# ArduinoUnoShield.net
KiCad netlist of a schematic drawn in Altium Designer
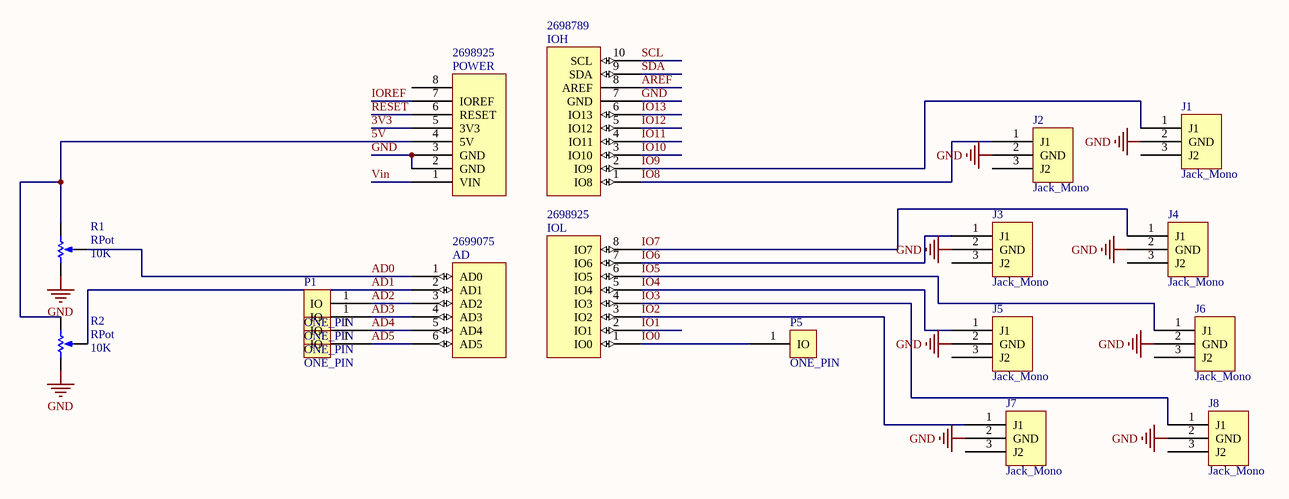
[diagram p0: ArduinoUnoShield.SchDoc]

(export (version "E")
  (design (tool "Eeschema 10.0.6"))
  (components
    (comp (ref "AD")
      (value "AD")
      (footprint "Header:Header 6x1 8.5mm")
      (fields (field (name "SUPPLIER PART NUMBER 4") "2699075"))
      (libsource (lib "Header") (part "AD"))
    )
    (comp (ref "IOH")
      (value "IOH")
      (footprint "Header:Header 10x1 8.5mm")
      (fields (field (name "SUPPLIER PART NUMBER 3") "2698789"))
      (libsource (lib "Header") (part "IOH"))
    )
    (comp (ref "IOL")
      (value "IOL")
      (footprint "Header 8x1 8.5mm")
      (fields (field (name "SUPPLIER PART NUMBER 4") "2698925"))
      (libsource (lib "Header") (part "IOL"))
    )
    (comp (ref "J1") (value "Jack_Mono") (footprint "JACK_MONO") (libsource (lib "Jack") (part "Jack_Mono")))
    (comp (ref "J2") (value "Jack_Mono") (footprint "JACK_MONO") (libsource (lib "Jack") (part "Jack_Mono")))
    (comp (ref "J3") (value "Jack_Mono") (footprint "JACK_MONO") (libsource (lib "Jack") (part "Jack_Mono")))
    (comp (ref "J4") (value "Jack_Mono") (footprint "JACK_MONO") (libsource (lib "Jack") (part "Jack_Mono")))
    (comp (ref "J5") (value "Jack_Mono") (footprint "JACK_MONO") (libsource (lib "Jack") (part "Jack_Mono")))
    (comp (ref "J6") (value "Jack_Mono") (footprint "JACK_MONO") (libsource (lib "Jack") (part "Jack_Mono")))
    (comp (ref "J7") (value "Jack_Mono") (footprint "JACK_MONO") (libsource (lib "Jack") (part "Jack_Mono")))
    (comp (ref "J8") (value "Jack_Mono") (footprint "JACK_MONO") (libsource (lib "Jack") (part "Jack_Mono")))
    (comp (ref "P1") (value "ONE_PIN") (footprint "ONE_PIN") (libsource (lib "") (part "ONE_PIN_1")))
    (comp (ref "P2") (value "ONE_PIN") (footprint "ONE_PIN") (libsource (lib "") (part "ONE_PIN_1")))
    (comp (ref "P3") (value "ONE_PIN") (footprint "ONE_PIN") (libsource (lib "") (part "ONE_PIN_1")))
    (comp (ref "P4") (value "ONE_PIN") (footprint "ONE_PIN") (libsource (lib "") (part "ONE_PIN_1")))
    (comp (ref "P5") (value "ONE_PIN") (footprint "ONE_PIN") (libsource (lib "OnePin") (part "ONE_PIN")))
    (comp (ref "POWER")
      (value "POWER_UNO")
      (footprint "Header 8x1 8.5mm")
      (fields (field (name "SUPPLIER PART NUMBER 4") "2698925"))
      (libsource (lib "Header") (part "POWER_UNO"))
    )
    (comp (ref "R1")
      (value "RPot")
      (footprint "VR5")
      (description "Potentiometer")
      (fields (field (name "ALTIUM_VALUE") "10K") (field (name "PUBLISHER") "Altium Limited"))
      (libsource (lib "Miscellaneous Devices") (part "RPot"))
    )
    (comp (ref "R2")
      (value "RPot")
      (footprint "VR5")
      (description "Potentiometer")
      (fields (field (name "ALTIUM_VALUE") "10K") (field (name "PUBLISHER") "Altium Limited"))
      (libsource (lib "Miscellaneous Devices") (part "RPot"))
    )
  )
  (nets
    (net (code "1") (name "/3V3") (class "Default")
      (node (ref "POWER") (pin "5") (pinfunction "3V3_5") (pintype "power_in"))
    )
    (net (code "2") (name "/5V") (class "Default")
      (node (ref "POWER") (pin "4") (pinfunction "5V_4") (pintype "power_in"))
      (node (ref "R1") (pin "2") (pinfunction "BOT_2") (pintype "passive"))
      (node (ref "R2") (pin "2") (pinfunction "BOT_2") (pintype "passive"))
    )
    (net (code "4") (name "/AD0") (class "Default")
      (node (ref "AD") (pin "1") (pinfunction "AD0_1") (pintype "bidirectional"))
      (node (ref "R1") (pin "3") (pinfunction "TAP_3") (pintype "passive"))
    )
    (net (code "5") (name "/AD1") (class "Default")
      (node (ref "AD") (pin "2") (pinfunction "AD1_2") (pintype "bidirectional"))
      (node (ref "R2") (pin "3") (pinfunction "TAP_3") (pintype "passive"))
    )
    (net (code "6") (name "/AD2") (class "Default")
      (node (ref "AD") (pin "3") (pinfunction "AD2_3") (pintype "bidirectional"))
      (node (ref "P1") (pin "1") (pinfunction "IO_1") (pintype "passive"))
    )
    (net (code "7") (name "/AD3") (class "Default")
      (node (ref "AD") (pin "4") (pinfunction "AD3_4") (pintype "bidirectional"))
      (node (ref "P2") (pin "1") (pinfunction "IO_1") (pintype "passive"))
    )
    (net (code "8") (name "/AD4") (class "Default")
      (node (ref "AD") (pin "5") (pinfunction "AD4_5") (pintype "bidirectional"))
      (node (ref "P3") (pin "1") (pinfunction "IO_1") (pintype "passive"))
    )
    (net (code "9") (name "/AD5") (class "Default")
      (node (ref "AD") (pin "6") (pinfunction "AD5_6") (pintype "bidirectional"))
      (node (ref "P4") (pin "1") (pinfunction "IO_1") (pintype "passive"))
    )
    (net (code "10") (name "/AREF") (class "Default")
      (node (ref "IOH") (pin "8") (pinfunction "AREF_8") (pintype "passive"))
    )
    (net (code "11") (name "/IO0") (class "Default")
      (node (ref "IOL") (pin "1") (pinfunction "IO0_1") (pintype "bidirectional"))
      (node (ref "P5") (pin "1") (pinfunction "IO_1") (pintype "passive"))
    )
    (net (code "12") (name "/IO1") (class "Default")
      (node (ref "IOL") (pin "2") (pinfunction "IO1_2") (pintype "bidirectional"))
    )
    (net (code "13") (name "/IO2") (class "Default")
      (node (ref "IOL") (pin "3") (pinfunction "IO2_3") (pintype "bidirectional"))
      (node (ref "J7") (pin "1") (pinfunction "J1_1") (pintype "passive"))
    )
    (net (code "14") (name "/IO3") (class "Default")
      (node (ref "IOL") (pin "4") (pinfunction "IO3_4") (pintype "bidirectional"))
      (node (ref "J8") (pin "1") (pinfunction "J1_1") (pintype "passive"))
    )
    (net (code "15") (name "/IO4") (class "Default")
      (node (ref "IOL") (pin "5") (pinfunction "IO4_5") (pintype "bidirectional"))
      (node (ref "J5") (pin "1") (pinfunction "J1_1") (pintype "passive"))
    )
    (net (code "16") (name "/IO5") (class "Default")
      (node (ref "IOL") (pin "6") (pinfunction "IO5_6") (pintype "bidirectional"))
      (node (ref "J6") (pin "1") (pinfunction "J1_1") (pintype "passive"))
    )
    (net (code "17") (name "/IO6") (class "Default")
      (node (ref "IOL") (pin "7") (pinfunction "IO6_7") (pintype "bidirectional"))
      (node (ref "J3") (pin "1") (pinfunction "J1_1") (pintype "passive"))
    )
    (net (code "18") (name "/IO7") (class "Default")
      (node (ref "IOL") (pin "8") (pinfunction "IO7_8") (pintype "bidirectional"))
      (node (ref "J4") (pin "1") (pinfunction "J1_1") (pintype "passive"))
    )
    (net (code "19") (name "/IO8") (class "Default")
      (node (ref "IOH") (pin "1") (pinfunction "IO8_1") (pintype "bidirectional"))
      (node (ref "J2") (pin "1") (pinfunction "J1_1") (pintype "passive"))
    )
    (net (code "20") (name "/IO9") (class "Default")
      (node (ref "IOH") (pin "2") (pinfunction "IO9_2") (pintype "bidirectional"))
      (node (ref "J1") (pin "1") (pinfunction "J1_1") (pintype "passive"))
    )
    (net (code "21") (name "/IO10") (class "Default")
      (node (ref "IOH") (pin "3") (pinfunction "IO10_3") (pintype "bidirectional"))
    )
    (net (code "22") (name "/IO11") (class "Default")
      (node (ref "IOH") (pin "4") (pinfunction "IO11_4") (pintype "bidirectional"))
    )
    (net (code "23") (name "/IO12") (class "Default")
      (node (ref "IOH") (pin "5") (pinfunction "IO12_5") (pintype "bidirectional"))
    )
    (net (code "24") (name "/IO13") (class "Default")
      (node (ref "IOH") (pin "6") (pinfunction "IO13_6") (pintype "bidirectional"))
    )
    (net (code "25") (name "/IOREF") (class "Default")
      (node (ref "POWER") (pin "7") (pinfunction "IOREF_7") (pintype "power_in"))
    )
    (net (code "26") (name "/RESET") (class "Default")
      (node (ref "POWER") (pin "6") (pinfunction "RESET_6") (pintype "passive"))
    )
    (net (code "27") (name "/SCL") (class "Default")
      (node (ref "IOH") (pin "10") (pinfunction "SCL_10") (pintype "bidirectional"))
    )
    (net (code "28") (name "/SDA") (class "Default")
      (node (ref "IOH") (pin "9") (pinfunction "SDA_9") (pintype "bidirectional"))
    )
    (net (code "29") (name "/Vin") (class "Default")
      (node (ref "POWER") (pin "1") (pinfunction "VIN_1") (pintype "power_in"))
    )
    (net (code "30") (name "GND") (class "Default")
      (node (ref "IOH") (pin "7") (pinfunction "GND_7") (pintype "power_in"))
      (node (ref "J1") (pin "2") (pinfunction "GND_2") (pintype "passive"))
      (node (ref "J2") (pin "2") (pinfunction "GND_2") (pintype "passive"))
      (node (ref "J3") (pin "2") (pinfunction "GND_2") (pintype "passive"))
      (node (ref "J4") (pin "2") (pinfunction "GND_2") (pintype "passive"))
      (node (ref "J5") (pin "2") (pinfunction "GND_2") (pintype "passive"))
      (node (ref "J6") (pin "2") (pinfunction "GND_2") (pintype "passive"))
      (node (ref "J7") (pin "2") (pinfunction "GND_2") (pintype "passive"))
      (node (ref "J8") (pin "2") (pinfunction "GND_2") (pintype "passive"))
      (node (ref "POWER") (pin "2") (pinfunction "GND_2") (pintype "power_in"))
      (node (ref "POWER") (pin "3") (pinfunction "GND_3") (pintype "power_in"))
      (node (ref "R1") (pin "1") (pinfunction "TOP_1") (pintype "passive"))
      (node (ref "R2") (pin "1") (pinfunction "TOP_1") (pintype "passive"))
    )
    (net (code "31") (name "unconnected-(J1-J2-Pad3)") (class "Default")
      (node (ref "J1") (pin "3") (pinfunction "J2_3") (pintype "passive"))
    )
    (net (code "32") (name "unconnected-(J2-J2-Pad3)") (class "Default")
      (node (ref "J2") (pin "3") (pinfunction "J2_3") (pintype "passive"))
    )
    (net (code "33") (name "unconnected-(J3-J2-Pad3)") (class "Default")
      (node (ref "J3") (pin "3") (pinfunction "J2_3") (pintype "passive"))
    )
    (net (code "34") (name "unconnected-(J4-J2-Pad3)") (class "Default")
      (node (ref "J4") (pin "3") (pinfunction "J2_3") (pintype "passive"))
    )
    (net (code "35") (name "unconnected-(J5-J2-Pad3)") (class "Default")
      (node (ref "J5") (pin "3") (pinfunction "J2_3") (pintype "passive"))
    )
    (net (code "36") (name "unconnected-(J6-J2-Pad3)") (class "Default")
      (node (ref "J6") (pin "3") (pinfunction "J2_3") (pintype "passive"))
    )
    (net (code "37") (name "unconnected-(J7-J2-Pad3)") (class "Default")
      (node (ref "J7") (pin "3") (pinfunction "J2_3") (pintype "passive"))
    )
    (net (code "38") (name "unconnected-(J8-J2-Pad3)") (class "Default")
      (node (ref "J8") (pin "3") (pinfunction "J2_3") (pintype "passive"))
    )
    (net (code "39") (name "unconnected-(POWER-Pad8)") (class "Default")
      (node (ref "POWER") (pin "8") (pintype "passive"))
    )
  )
)
